# batteryAdapterBoard_r001.net
KiCad netlist of a schematic drawn in Altium Designer
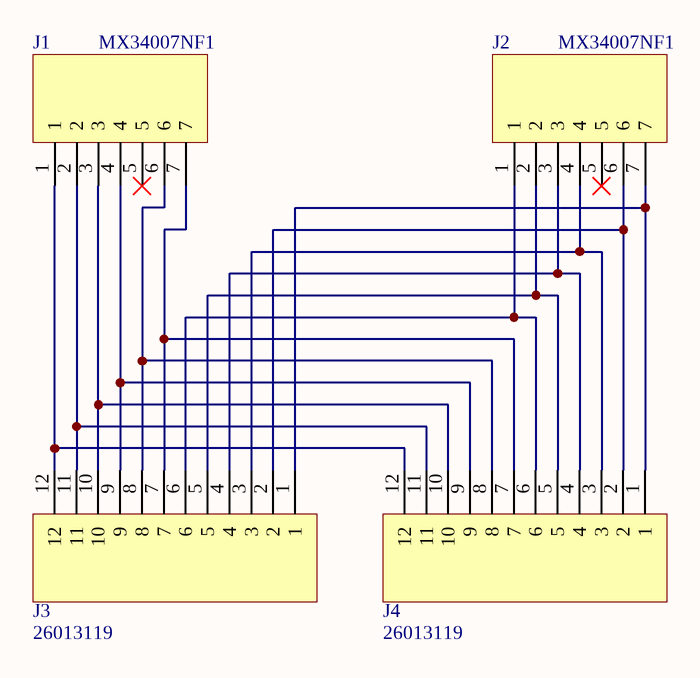
[diagram p0: batteryAdapterBoard_r001.SchDoc]

(export (version "E")
  (design (tool "Eeschema 10.0.6"))
  (components
    (comp (ref "J1")
      (value "MX34007NF1")
      (footprint "MX34007NF1")
      (libsource (lib "BublykIntegratedLibrary") (part "MX34007NF1"))
    )
    (comp (ref "J2")
      (value "MX34007NF1")
      (footprint "MX34007NF1")
      (libsource (lib "BublykIntegratedLibrary") (part "MX34007NF1"))
    )
    (comp (ref "J3")
      (value "26013119")
      (footprint "26013119")
      (libsource (lib "BublykIntegratedLibrary") (part "26013119"))
    )
    (comp (ref "J4")
      (value "26013119")
      (footprint "26013119")
      (libsource (lib "BublykIntegratedLibrary") (part "26013119"))
    )
  )
  (nets
    (net (code "1") (name "Net-(J1-Pad1)") (class "Default")
      (node (ref "J1") (pin "1") (pinfunction "1_1") (pintype "passive"))
      (node (ref "J3") (pin "12") (pinfunction "12_12") (pintype "passive"))
      (node (ref "J4") (pin "12") (pinfunction "12_12") (pintype "passive"))
    )
    (net (code "2") (name "Net-(J1-Pad2)") (class "Default")
      (node (ref "J1") (pin "2") (pinfunction "2_2") (pintype "passive"))
      (node (ref "J3") (pin "11") (pinfunction "11_11") (pintype "passive"))
      (node (ref "J4") (pin "11") (pinfunction "11_11") (pintype "passive"))
    )
    (net (code "3") (name "Net-(J1-Pad3)") (class "Default")
      (node (ref "J1") (pin "3") (pinfunction "3_3") (pintype "passive"))
      (node (ref "J3") (pin "10") (pinfunction "10_10") (pintype "passive"))
      (node (ref "J4") (pin "10") (pinfunction "10_10") (pintype "passive"))
    )
    (net (code "4") (name "Net-(J1-Pad4)") (class "Default")
      (node (ref "J1") (pin "4") (pinfunction "4_4") (pintype "passive"))
      (node (ref "J3") (pin "9") (pinfunction "9_9") (pintype "passive"))
      (node (ref "J4") (pin "9") (pinfunction "9_9") (pintype "passive"))
    )
    (net (code "5") (name "Net-(J1-Pad6)") (class "Default")
      (node (ref "J1") (pin "6") (pinfunction "6_6") (pintype "passive"))
      (node (ref "J3") (pin "8") (pinfunction "8_8") (pintype "passive"))
      (node (ref "J4") (pin "8") (pinfunction "8_8") (pintype "passive"))
    )
    (net (code "6") (name "Net-(J1-Pad7)") (class "Default")
      (node (ref "J1") (pin "7") (pinfunction "7_7") (pintype "passive"))
      (node (ref "J3") (pin "7") (pinfunction "7_7") (pintype "passive"))
      (node (ref "J4") (pin "7") (pinfunction "7_7") (pintype "passive"))
    )
    (net (code "7") (name "Net-(J2-Pad1)") (class "Default")
      (node (ref "J2") (pin "1") (pinfunction "1_1") (pintype "passive"))
      (node (ref "J3") (pin "6") (pinfunction "6_6") (pintype "passive"))
      (node (ref "J4") (pin "6") (pinfunction "6_6") (pintype "passive"))
    )
    (net (code "8") (name "Net-(J2-Pad2)") (class "Default")
      (node (ref "J2") (pin "2") (pinfunction "2_2") (pintype "passive"))
      (node (ref "J3") (pin "5") (pinfunction "5_5") (pintype "passive"))
      (node (ref "J4") (pin "5") (pinfunction "5_5") (pintype "passive"))
    )
    (net (code "9") (name "Net-(J2-Pad3)") (class "Default")
      (node (ref "J2") (pin "3") (pinfunction "3_3") (pintype "passive"))
      (node (ref "J3") (pin "4") (pinfunction "4_4") (pintype "passive"))
      (node (ref "J4") (pin "4") (pinfunction "4_4") (pintype "passive"))
    )
    (net (code "10") (name "Net-(J2-Pad4)") (class "Default")
      (node (ref "J2") (pin "4") (pinfunction "4_4") (pintype "passive"))
      (node (ref "J3") (pin "3") (pinfunction "3_3") (pintype "passive"))
      (node (ref "J4") (pin "3") (pinfunction "3_3") (pintype "passive"))
    )
    (net (code "11") (name "Net-(J2-Pad6)") (class "Default")
      (node (ref "J2") (pin "6") (pinfunction "6_6") (pintype "passive"))
      (node (ref "J3") (pin "2") (pinfunction "2_2") (pintype "passive"))
      (node (ref "J4") (pin "2") (pinfunction "2_2") (pintype "passive"))
    )
    (net (code "12") (name "Net-(J2-Pad7)") (class "Default")
      (node (ref "J2") (pin "7") (pinfunction "7_7") (pintype "passive"))
      (node (ref "J3") (pin "1") (pinfunction "1_1") (pintype "passive"))
      (node (ref "J4") (pin "1") (pinfunction "1_1") (pintype "passive"))
    )
    (net (code "13") (name "unconnected-(J1-Pad5)") (class "Default")
      (node (ref "J1") (pin "5") (pinfunction "5_5") (pintype "passive+no_connect"))
    )
    (net (code "14") (name "unconnected-(J2-Pad5)") (class "Default")
      (node (ref "J2") (pin "5") (pinfunction "5_5") (pintype "passive+no_connect"))
    )
  )
)
